# InterfaceConnector.net
KiCad netlist of a schematic drawn in Altium Designer
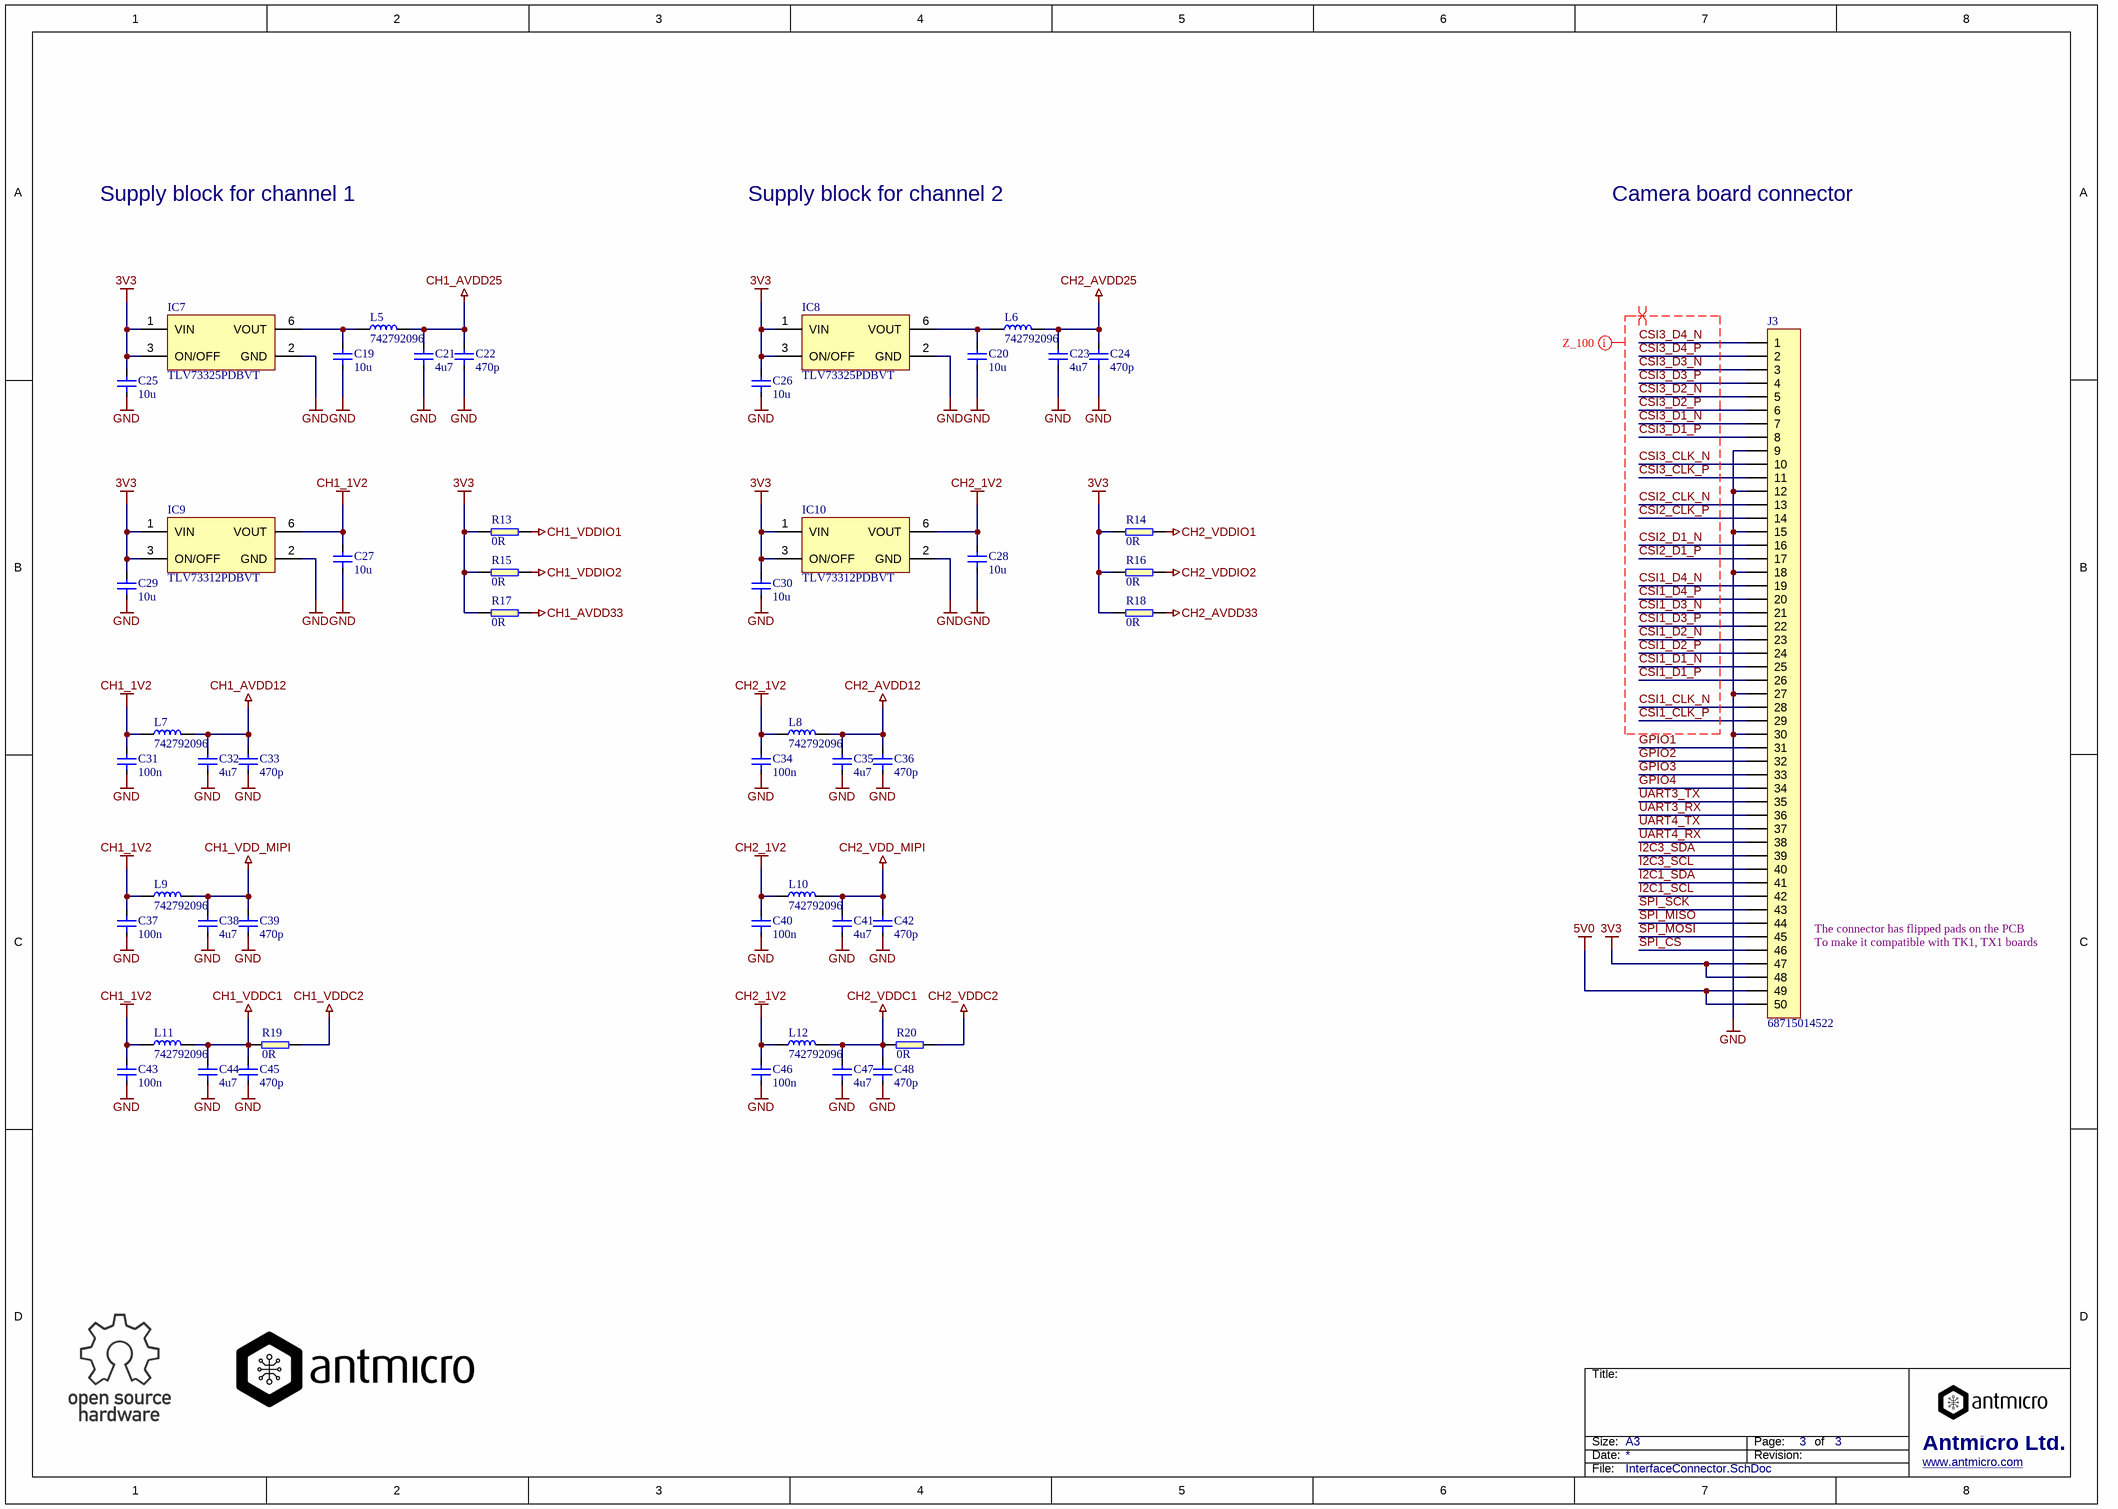
[diagram p0: InterfaceConnector.SchDoc]

(export (version "E")
  (design (tool "Eeschema 10.0.6"))
  (components
    (comp (ref "C19")
      (value "10u")
      (footprint "HDMI-MIPI-Bridge:0603")
      (description "MLCC SMT Capacitor 10uF 0603")
      (fields (field (name "PART NUMBER") "C_10u_0603") (field (name "MANUFACTURER") "MULTICOMP"))
      (libsource (lib "AntmicroComponents") (part "C"))
    )
    (comp (ref "C20")
      (value "10u")
      (footprint "HDMI-MIPI-Bridge:0603")
      (description "MLCC SMT Capacitor 10uF 0603")
      (fields (field (name "PART NUMBER") "C_10u_0603") (field (name "MANUFACTURER") "MULTICOMP"))
      (libsource (lib "AntmicroComponents") (part "C"))
    )
    (comp (ref "C21")
      (value "4u7")
      (footprint "HDMI-MIPI-Bridge:0402")
      (description "MLCC SMT Capacitor 4u7F 0603")
      (fields (field (name "PART NUMBER") "C_4u7_0402") (field (name "MANUFACTURER") "MURATA"))
      (libsource (lib "AntmicroComponents") (part "C"))
    )
    (comp (ref "C22")
      (value "470p")
      (footprint "HDMI-MIPI-Bridge:0402")
      (description "MLCC SMT Capacitor 470pF 0402")
      (fields (field (name "PART NUMBER") "C_470p_0402") (field (name "MANUFACTURER") "MULTICOMP"))
      (libsource (lib "AntmicroComponents") (part "C"))
    )
    (comp (ref "C23")
      (value "4u7")
      (footprint "HDMI-MIPI-Bridge:0402")
      (description "MLCC SMT Capacitor 4u7F 0603")
      (fields (field (name "PART NUMBER") "C_4u7_0402") (field (name "MANUFACTURER") "MURATA"))
      (libsource (lib "AntmicroComponents") (part "C"))
    )
    (comp (ref "C24")
      (value "470p")
      (footprint "HDMI-MIPI-Bridge:0402")
      (description "MLCC SMT Capacitor 470pF 0402")
      (fields (field (name "PART NUMBER") "C_470p_0402") (field (name "MANUFACTURER") "MULTICOMP"))
      (libsource (lib "AntmicroComponents") (part "C"))
    )
    (comp (ref "C25")
      (value "10u")
      (footprint "HDMI-MIPI-Bridge:0603")
      (description "MLCC SMT Capacitor 10uF 0603")
      (fields (field (name "PART NUMBER") "C_10u_0603") (field (name "MANUFACTURER") "MULTICOMP"))
      (libsource (lib "AntmicroComponents") (part "C"))
    )
    (comp (ref "C26")
      (value "10u")
      (footprint "HDMI-MIPI-Bridge:0603")
      (description "MLCC SMT Capacitor 10uF 0603")
      (fields (field (name "PART NUMBER") "C_10u_0603") (field (name "MANUFACTURER") "MULTICOMP"))
      (libsource (lib "AntmicroComponents") (part "C"))
    )
    (comp (ref "C27")
      (value "10u")
      (footprint "HDMI-MIPI-Bridge:0603")
      (description "MLCC SMT Capacitor 10uF 0603")
      (fields (field (name "PART NUMBER") "C_10u_0603") (field (name "MANUFACTURER") "MULTICOMP"))
      (libsource (lib "AntmicroComponents") (part "C"))
    )
    (comp (ref "C28")
      (value "10u")
      (footprint "HDMI-MIPI-Bridge:0603")
      (description "MLCC SMT Capacitor 10uF 0603")
      (fields (field (name "PART NUMBER") "C_10u_0603") (field (name "MANUFACTURER") "MULTICOMP"))
      (libsource (lib "AntmicroComponents") (part "C"))
    )
    (comp (ref "C29")
      (value "10u")
      (footprint "HDMI-MIPI-Bridge:0603")
      (description "MLCC SMT Capacitor 10uF 0603")
      (fields (field (name "PART NUMBER") "C_10u_0603") (field (name "MANUFACTURER") "MULTICOMP"))
      (libsource (lib "AntmicroComponents") (part "C"))
    )
    (comp (ref "C30")
      (value "10u")
      (footprint "HDMI-MIPI-Bridge:0603")
      (description "MLCC SMT Capacitor 10uF 0603")
      (fields (field (name "PART NUMBER") "C_10u_0603") (field (name "MANUFACTURER") "MULTICOMP"))
      (libsource (lib "AntmicroComponents") (part "C"))
    )
    (comp (ref "C31")
      (value "100n")
      (footprint "HDMI-MIPI-Bridge:0402")
      (description "MLCC SMT Capacitor 100nF 0402")
      (fields (field (name "PART NUMBER") "C_100n_0402") (field (name "MANUFACTURER") "MULTICOMP"))
      (libsource (lib "AntmicroComponents") (part "C"))
    )
    (comp (ref "C32")
      (value "4u7")
      (footprint "HDMI-MIPI-Bridge:0402")
      (description "MLCC SMT Capacitor 4u7F 0603")
      (fields (field (name "PART NUMBER") "C_4u7_0402") (field (name "MANUFACTURER") "MURATA"))
      (libsource (lib "AntmicroComponents") (part "C"))
    )
    (comp (ref "C33")
      (value "470p")
      (footprint "HDMI-MIPI-Bridge:0402")
      (description "MLCC SMT Capacitor 470pF 0402")
      (fields (field (name "PART NUMBER") "C_470p_0402") (field (name "MANUFACTURER") "MULTICOMP"))
      (libsource (lib "AntmicroComponents") (part "C"))
    )
    (comp (ref "C34")
      (value "100n")
      (footprint "HDMI-MIPI-Bridge:0402")
      (description "MLCC SMT Capacitor 100nF 0402")
      (fields (field (name "PART NUMBER") "C_100n_0402") (field (name "MANUFACTURER") "MULTICOMP"))
      (libsource (lib "AntmicroComponents") (part "C"))
    )
    (comp (ref "C35")
      (value "4u7")
      (footprint "HDMI-MIPI-Bridge:0402")
      (description "MLCC SMT Capacitor 4u7F 0603")
      (fields (field (name "PART NUMBER") "C_4u7_0402") (field (name "MANUFACTURER") "MURATA"))
      (libsource (lib "AntmicroComponents") (part "C"))
    )
    (comp (ref "C36")
      (value "470p")
      (footprint "HDMI-MIPI-Bridge:0402")
      (description "MLCC SMT Capacitor 470pF 0402")
      (fields (field (name "PART NUMBER") "C_470p_0402") (field (name "MANUFACTURER") "MULTICOMP"))
      (libsource (lib "AntmicroComponents") (part "C"))
    )
    (comp (ref "C37")
      (value "100n")
      (footprint "HDMI-MIPI-Bridge:0402")
      (description "MLCC SMT Capacitor 100nF 0402")
      (fields (field (name "PART NUMBER") "C_100n_0402") (field (name "MANUFACTURER") "MULTICOMP"))
      (libsource (lib "AntmicroComponents") (part "C"))
    )
    (comp (ref "C38")
      (value "4u7")
      (footprint "HDMI-MIPI-Bridge:0402")
      (description "MLCC SMT Capacitor 4u7F 0603")
      (fields (field (name "PART NUMBER") "C_4u7_0402") (field (name "MANUFACTURER") "MURATA"))
      (libsource (lib "AntmicroComponents") (part "C"))
    )
    (comp (ref "C39")
      (value "470p")
      (footprint "HDMI-MIPI-Bridge:0402")
      (description "MLCC SMT Capacitor 470pF 0402")
      (fields (field (name "PART NUMBER") "C_470p_0402") (field (name "MANUFACTURER") "MULTICOMP"))
      (libsource (lib "AntmicroComponents") (part "C"))
    )
    (comp (ref "C40")
      (value "100n")
      (footprint "HDMI-MIPI-Bridge:0402")
      (description "MLCC SMT Capacitor 100nF 0402")
      (fields (field (name "PART NUMBER") "C_100n_0402") (field (name "MANUFACTURER") "MULTICOMP"))
      (libsource (lib "AntmicroComponents") (part "C"))
    )
    (comp (ref "C41")
      (value "4u7")
      (footprint "HDMI-MIPI-Bridge:0402")
      (description "MLCC SMT Capacitor 4u7F 0603")
      (fields (field (name "PART NUMBER") "C_4u7_0402") (field (name "MANUFACTURER") "MURATA"))
      (libsource (lib "AntmicroComponents") (part "C"))
    )
    (comp (ref "C42")
      (value "470p")
      (footprint "HDMI-MIPI-Bridge:0402")
      (description "MLCC SMT Capacitor 470pF 0402")
      (fields (field (name "PART NUMBER") "C_470p_0402") (field (name "MANUFACTURER") "MULTICOMP"))
      (libsource (lib "AntmicroComponents") (part "C"))
    )
    (comp (ref "C43")
      (value "100n")
      (footprint "HDMI-MIPI-Bridge:0402")
      (description "MLCC SMT Capacitor 100nF 0402")
      (fields (field (name "PART NUMBER") "C_100n_0402") (field (name "MANUFACTURER") "MULTICOMP"))
      (libsource (lib "AntmicroComponents") (part "C"))
    )
    (comp (ref "C44")
      (value "4u7")
      (footprint "HDMI-MIPI-Bridge:0402")
      (description "MLCC SMT Capacitor 4u7F 0603")
      (fields (field (name "PART NUMBER") "C_4u7_0402") (field (name "MANUFACTURER") "MURATA"))
      (libsource (lib "AntmicroComponents") (part "C"))
    )
    (comp (ref "C45")
      (value "470p")
      (footprint "HDMI-MIPI-Bridge:0402")
      (description "MLCC SMT Capacitor 470pF 0402")
      (fields (field (name "PART NUMBER") "C_470p_0402") (field (name "MANUFACTURER") "MULTICOMP"))
      (libsource (lib "AntmicroComponents") (part "C"))
    )
    (comp (ref "C46")
      (value "100n")
      (footprint "HDMI-MIPI-Bridge:0402")
      (description "MLCC SMT Capacitor 100nF 0402")
      (fields (field (name "PART NUMBER") "C_100n_0402") (field (name "MANUFACTURER") "MULTICOMP"))
      (libsource (lib "AntmicroComponents") (part "C"))
    )
    (comp (ref "C47")
      (value "4u7")
      (footprint "HDMI-MIPI-Bridge:0402")
      (description "MLCC SMT Capacitor 4u7F 0603")
      (fields (field (name "PART NUMBER") "C_4u7_0402") (field (name "MANUFACTURER") "MURATA"))
      (libsource (lib "AntmicroComponents") (part "C"))
    )
    (comp (ref "C48")
      (value "470p")
      (footprint "HDMI-MIPI-Bridge:0402")
      (description "MLCC SMT Capacitor 470pF 0402")
      (fields (field (name "PART NUMBER") "C_470p_0402") (field (name "MANUFACTURER") "MULTICOMP"))
      (libsource (lib "AntmicroComponents") (part "C"))
    )
    (comp (ref "IC7")
      (value "TLV73325PDBVT")
      (footprint "HDMI-MIPI-Bridge:SOT23-5N")
      (description "Linear Voltage Regulator IC Positive Fixed Output 2.5V 300mA SOT-23-5")
      (fields (field (name "MANUFACTURER") "TEXAS INSTRUMENTS"))
      (libsource (lib "AntmicroComponents") (part "VREG_EN"))
    )
    (comp (ref "IC8")
      (value "TLV73325PDBVT")
      (footprint "HDMI-MIPI-Bridge:SOT23-5N")
      (description "Linear Voltage Regulator IC Positive Fixed Output 2.5V 300mA SOT-23-5")
      (fields (field (name "MANUFACTURER") "TEXAS INSTRUMENTS"))
      (libsource (lib "AntmicroComponents") (part "VREG_EN"))
    )
    (comp (ref "IC9")
      (value "TLV73312PDBVT")
      (footprint "HDMI-MIPI-Bridge:SOT23-5N")
      (description "Linear Voltage Regulator IC Positive Fixed Output 3.3V 300mA SOT-23-5")
      (fields (field (name "MANUFACTURER") "TEXAS INSTRUMENTS"))
      (libsource (lib "AntmicroComponents") (part "VREG_EN"))
    )
    (comp (ref "IC10")
      (value "TLV73312PDBVT")
      (footprint "HDMI-MIPI-Bridge:SOT23-5N")
      (description "Linear Voltage Regulator IC Positive Fixed Output 3.3V 300mA SOT-23-5")
      (fields (field (name "MANUFACTURER") "TEXAS INSTRUMENTS"))
      (libsource (lib "AntmicroComponents") (part "VREG_EN"))
    )
    (comp (ref "J3")
      (value "68715014522")
      (footprint "HDMI-MIPI-Bridge:68715014522_FLIPPED")
      (description "0.50mm SMT ZIF Horizontal Bottom Contact WR-FPC")
      (fields
        (field (name "PART NUMBER") "WE-687-150-145-22_FLIPPED")
        (field (name "MANUFACTURER") "WURTH ELEKTRONIK")
      )
      (libsource (lib "AntmicroComponents") (part "1X50"))
    )
    (comp (ref "L5")
      (value "742792096")
      (footprint "HDMI-MIPI-Bridge:0805")
      (description "FERRITE BEAD, 1kOhm 1A")
      (fields (field (name "PART NUMBER") "Wurth-742792096") (field (name "MANUFACTURER") "WURTH ELEKTRONIK"))
      (libsource (lib "AntmicroComponents") (part "Inductor SMT"))
    )
    (comp (ref "L6")
      (value "742792096")
      (footprint "HDMI-MIPI-Bridge:0805")
      (description "FERRITE BEAD, 1kOhm 1A")
      (fields (field (name "PART NUMBER") "Wurth-742792096") (field (name "MANUFACTURER") "WURTH ELEKTRONIK"))
      (libsource (lib "AntmicroComponents") (part "Inductor SMT"))
    )
    (comp (ref "L7")
      (value "742792096")
      (footprint "HDMI-MIPI-Bridge:0805")
      (description "FERRITE BEAD, 1kOhm 1A")
      (fields (field (name "PART NUMBER") "Wurth-742792096") (field (name "MANUFACTURER") "WURTH ELEKTRONIK"))
      (libsource (lib "AntmicroComponents") (part "Inductor SMT"))
    )
    (comp (ref "L8")
      (value "742792096")
      (footprint "HDMI-MIPI-Bridge:0805")
      (description "FERRITE BEAD, 1kOhm 1A")
      (fields (field (name "PART NUMBER") "Wurth-742792096") (field (name "MANUFACTURER") "WURTH ELEKTRONIK"))
      (libsource (lib "AntmicroComponents") (part "Inductor SMT"))
    )
    (comp (ref "L9")
      (value "742792096")
      (footprint "HDMI-MIPI-Bridge:0805")
      (description "FERRITE BEAD, 1kOhm 1A")
      (fields (field (name "PART NUMBER") "Wurth-742792096") (field (name "MANUFACTURER") "WURTH ELEKTRONIK"))
      (libsource (lib "AntmicroComponents") (part "Inductor SMT"))
    )
    (comp (ref "L10")
      (value "742792096")
      (footprint "HDMI-MIPI-Bridge:0805")
      (description "FERRITE BEAD, 1kOhm 1A")
      (fields (field (name "PART NUMBER") "Wurth-742792096") (field (name "MANUFACTURER") "WURTH ELEKTRONIK"))
      (libsource (lib "AntmicroComponents") (part "Inductor SMT"))
    )
    (comp (ref "L11")
      (value "742792096")
      (footprint "HDMI-MIPI-Bridge:0805")
      (description "FERRITE BEAD, 1kOhm 1A")
      (fields (field (name "PART NUMBER") "Wurth-742792096") (field (name "MANUFACTURER") "WURTH ELEKTRONIK"))
      (libsource (lib "AntmicroComponents") (part "Inductor SMT"))
    )
    (comp (ref "L12")
      (value "742792096")
      (footprint "HDMI-MIPI-Bridge:0805")
      (description "FERRITE BEAD, 1kOhm 1A")
      (fields (field (name "PART NUMBER") "Wurth-742792096") (field (name "MANUFACTURER") "WURTH ELEKTRONIK"))
      (libsource (lib "AntmicroComponents") (part "Inductor SMT"))
    )
    (comp (ref "R13")
      (value "0R")
      (footprint "HDMI-MIPI-Bridge:0603")
      (description "SMT Resistor 0R 0603")
      (fields (field (name "PART NUMBER") "R_0R_0603") (field (name "MANUFACTURER") "BOURNS"))
      (libsource (lib "AntmicroComponents") (part "R"))
    )
    (comp (ref "R14")
      (value "0R")
      (footprint "HDMI-MIPI-Bridge:0603")
      (description "SMT Resistor 0R 0603")
      (fields (field (name "PART NUMBER") "R_0R_0603") (field (name "MANUFACTURER") "BOURNS"))
      (libsource (lib "AntmicroComponents") (part "R"))
    )
    (comp (ref "R15")
      (value "0R")
      (footprint "HDMI-MIPI-Bridge:0603")
      (description "SMT Resistor 0R 0603")
      (fields (field (name "PART NUMBER") "R_0R_0603") (field (name "MANUFACTURER") "BOURNS"))
      (libsource (lib "AntmicroComponents") (part "R"))
    )
    (comp (ref "R16")
      (value "0R")
      (footprint "HDMI-MIPI-Bridge:0603")
      (description "SMT Resistor 0R 0603")
      (fields (field (name "PART NUMBER") "R_0R_0603") (field (name "MANUFACTURER") "BOURNS"))
      (libsource (lib "AntmicroComponents") (part "R"))
    )
    (comp (ref "R17")
      (value "0R")
      (footprint "HDMI-MIPI-Bridge:0603")
      (description "SMT Resistor 0R 0603")
      (fields (field (name "PART NUMBER") "R_0R_0603") (field (name "MANUFACTURER") "BOURNS"))
      (libsource (lib "AntmicroComponents") (part "R"))
    )
    (comp (ref "R18")
      (value "0R")
      (footprint "HDMI-MIPI-Bridge:0603")
      (description "SMT Resistor 0R 0603")
      (fields (field (name "PART NUMBER") "R_0R_0603") (field (name "MANUFACTURER") "BOURNS"))
      (libsource (lib "AntmicroComponents") (part "R"))
    )
    (comp (ref "R19")
      (value "0R")
      (footprint "HDMI-MIPI-Bridge:0603")
      (description "SMT Resistor 0R 0603")
      (fields (field (name "PART NUMBER") "R_0R_0603") (field (name "MANUFACTURER") "BOURNS"))
      (libsource (lib "AntmicroComponents") (part "R"))
    )
    (comp (ref "R20")
      (value "0R")
      (footprint "HDMI-MIPI-Bridge:0603")
      (description "SMT Resistor 0R 0603")
      (fields (field (name "PART NUMBER") "R_0R_0603") (field (name "MANUFACTURER") "BOURNS"))
      (libsource (lib "AntmicroComponents") (part "R"))
    )
  )
  (nets
    (net (code "1") (name "/CSI1_CLK_N") (class "Default")
      (node (ref "J3") (pin "28") (pinfunction "28_28") (pintype "passive"))
    )
    (net (code "2") (name "/CSI1_CLK_P") (class "Default")
      (node (ref "J3") (pin "29") (pinfunction "29_29") (pintype "passive"))
    )
    (net (code "3") (name "/CSI1_D1_N") (class "Default")
      (node (ref "J3") (pin "25") (pinfunction "25_25") (pintype "passive"))
    )
    (net (code "4") (name "/CSI1_D1_P") (class "Default")
      (node (ref "J3") (pin "26") (pinfunction "26_26") (pintype "passive"))
    )
    (net (code "5") (name "/CSI1_D2_N") (class "Default")
      (node (ref "J3") (pin "23") (pinfunction "23_23") (pintype "passive"))
    )
    (net (code "6") (name "/CSI1_D2_P") (class "Default")
      (node (ref "J3") (pin "24") (pinfunction "24_24") (pintype "passive"))
    )
    (net (code "7") (name "/CSI1_D3_N") (class "Default")
      (node (ref "J3") (pin "21") (pinfunction "21_21") (pintype "passive"))
    )
    (net (code "8") (name "/CSI1_D3_P") (class "Default")
      (node (ref "J3") (pin "22") (pinfunction "22_22") (pintype "passive"))
    )
    (net (code "9") (name "/CSI1_D4_N") (class "Default")
      (node (ref "J3") (pin "19") (pinfunction "19_19") (pintype "passive"))
    )
    (net (code "10") (name "/CSI1_D4_P") (class "Default")
      (node (ref "J3") (pin "20") (pinfunction "20_20") (pintype "passive"))
    )
    (net (code "11") (name "/CSI2_CLK_N") (class "Default")
      (node (ref "J3") (pin "13") (pinfunction "13_13") (pintype "passive"))
    )
    (net (code "12") (name "/CSI2_CLK_P") (class "Default")
      (node (ref "J3") (pin "14") (pinfunction "14_14") (pintype "passive"))
    )
    (net (code "13") (name "/CSI2_D1_N") (class "Default")
      (node (ref "J3") (pin "16") (pinfunction "16_16") (pintype "passive"))
    )
    (net (code "14") (name "/CSI2_D1_P") (class "Default")
      (node (ref "J3") (pin "17") (pinfunction "17_17") (pintype "passive"))
    )
    (net (code "15") (name "/CSI3_CLK_N") (class "Default")
      (node (ref "J3") (pin "10") (pinfunction "10_10") (pintype "passive"))
    )
    (net (code "16") (name "/CSI3_CLK_P") (class "Default")
      (node (ref "J3") (pin "11") (pinfunction "11_11") (pintype "passive"))
    )
    (net (code "17") (name "/CSI3_D1_N") (class "Default")
      (node (ref "J3") (pin "7") (pinfunction "7_7") (pintype "passive"))
    )
    (net (code "18") (name "/CSI3_D1_P") (class "Default")
      (node (ref "J3") (pin "8") (pinfunction "8_8") (pintype "passive"))
    )
    (net (code "19") (name "/CSI3_D2_N") (class "Default")
      (node (ref "J3") (pin "5") (pinfunction "5_5") (pintype "passive"))
    )
    (net (code "20") (name "/CSI3_D2_P") (class "Default")
      (node (ref "J3") (pin "6") (pinfunction "6_6") (pintype "passive"))
    )
    (net (code "21") (name "/CSI3_D3_N") (class "Default")
      (node (ref "J3") (pin "3") (pinfunction "3_3") (pintype "passive"))
    )
    (net (code "22") (name "/CSI3_D3_P") (class "Default")
      (node (ref "J3") (pin "4") (pinfunction "4_4") (pintype "passive"))
    )
    (net (code "23") (name "/CSI3_D4_N") (class "Default")
      (node (ref "J3") (pin "1") (pinfunction "1_1") (pintype "passive"))
    )
    (net (code "24") (name "/CSI3_D4_P") (class "Default")
      (node (ref "J3") (pin "2") (pinfunction "2_2") (pintype "passive"))
    )
    (net (code "25") (name "/GPIO1") (class "Default")
      (node (ref "J3") (pin "31") (pinfunction "31_31") (pintype "passive"))
    )
    (net (code "26") (name "/GPIO2") (class "Default")
      (node (ref "J3") (pin "32") (pinfunction "32_32") (pintype "passive"))
    )
    (net (code "27") (name "/GPIO3") (class "Default")
      (node (ref "J3") (pin "33") (pinfunction "33_33") (pintype "passive"))
    )
    (net (code "28") (name "/GPIO4") (class "Default")
      (node (ref "J3") (pin "34") (pinfunction "34_34") (pintype "passive"))
    )
    (net (code "29") (name "/I2C1_SCL") (class "Default")
      (node (ref "J3") (pin "42") (pinfunction "42_42") (pintype "passive"))
    )
    (net (code "30") (name "/I2C1_SDA") (class "Default")
      (node (ref "J3") (pin "41") (pinfunction "41_41") (pintype "passive"))
    )
    (net (code "31") (name "/I2C3_SCL") (class "Default")
      (node (ref "J3") (pin "40") (pinfunction "40_40") (pintype "passive"))
    )
    (net (code "32") (name "/I2C3_SDA") (class "Default")
      (node (ref "J3") (pin "39") (pinfunction "39_39") (pintype "passive"))
    )
    (net (code "33") (name "/SPI_CS") (class "Default")
      (node (ref "J3") (pin "46") (pinfunction "46_46") (pintype "passive"))
    )
    (net (code "34") (name "/SPI_MISO") (class "Default")
      (node (ref "J3") (pin "44") (pinfunction "44_44") (pintype "passive"))
    )
    (net (code "35") (name "/SPI_MOSI") (class "Default")
      (node (ref "J3") (pin "45") (pinfunction "45_45") (pintype "passive"))
    )
    (net (code "36") (name "/SPI_SCK") (class "Default")
      (node (ref "J3") (pin "43") (pinfunction "43_43") (pintype "passive"))
    )
    (net (code "37") (name "/UART3_RX") (class "Default")
      (node (ref "J3") (pin "36") (pinfunction "36_36") (pintype "passive"))
    )
    (net (code "38") (name "/UART3_TX") (class "Default")
      (node (ref "J3") (pin "35") (pinfunction "35_35") (pintype "passive"))
    )
    (net (code "39") (name "/UART4_RX") (class "Default")
      (node (ref "J3") (pin "38") (pinfunction "38_38") (pintype "passive"))
    )
    (net (code "40") (name "/UART4_TX") (class "Default")
      (node (ref "J3") (pin "37") (pinfunction "37_37") (pintype "passive"))
    )
    (net (code "41") (name "3V3") (class "Default")
      (node (ref "C25") (pin "2") (pinfunction "2_2") (pintype "passive"))
      (node (ref "C26") (pin "2") (pinfunction "2_2") (pintype "passive"))
      (node (ref "C29") (pin "2") (pinfunction "2_2") (pintype "passive"))
      (node (ref "C30") (pin "2") (pinfunction "2_2") (pintype "passive"))
      (node (ref "IC10") (pin "1") (pinfunction "VIN_1") (pintype "passive"))
      (node (ref "IC10") (pin "3") (pinfunction "ON/OFF_3") (pintype "passive"))
      (node (ref "IC7") (pin "1") (pinfunction "VIN_1") (pintype "passive"))
      (node (ref "IC7") (pin "3") (pinfunction "ON/OFF_3") (pintype "passive"))
      (node (ref "IC8") (pin "1") (pinfunction "VIN_1") (pintype "passive"))
      (node (ref "IC8") (pin "3") (pinfunction "ON/OFF_3") (pintype "passive"))
      (node (ref "IC9") (pin "1") (pinfunction "VIN_1") (pintype "passive"))
      (node (ref "IC9") (pin "3") (pinfunction "ON/OFF_3") (pintype "passive"))
      (node (ref "J3") (pin "47") (pinfunction "47_47") (pintype "passive"))
      (node (ref "J3") (pin "48") (pinfunction "48_48") (pintype "passive"))
      (node (ref "R13") (pin "1") (pintype "passive"))
      (node (ref "R14") (pin "1") (pintype "passive"))
      (node (ref "R15") (pin "1") (pintype "passive"))
      (node (ref "R16") (pin "1") (pintype "passive"))
      (node (ref "R17") (pin "1") (pintype "passive"))
      (node (ref "R18") (pin "1") (pintype "passive"))
    )
    (net (code "42") (name "5V0") (class "Default")
      (node (ref "J3") (pin "49") (pinfunction "49_49") (pintype "passive"))
      (node (ref "J3") (pin "50") (pinfunction "50_50") (pintype "passive"))
    )
    (net (code "43") (name "CH1_1V2") (class "Default")
      (node (ref "C27") (pin "2") (pinfunction "2_2") (pintype "passive"))
      (node (ref "C31") (pin "2") (pinfunction "2_2") (pintype "passive"))
      (node (ref "C37") (pin "2") (pinfunction "2_2") (pintype "passive"))
      (node (ref "C43") (pin "2") (pinfunction "2_2") (pintype "passive"))
      (node (ref "IC9") (pin "6") (pinfunction "VOUT_6") (pintype "passive"))
      (node (ref "L11") (pin "1") (pintype "passive"))
      (node (ref "L7") (pin "1") (pintype "passive"))
      (node (ref "L9") (pin "1") (pintype "passive"))
    )
    (net (code "44") (name "CH1_AVDD12") (class "Default")
      (node (ref "C32") (pin "2") (pinfunction "2_2") (pintype "passive"))
      (node (ref "C33") (pin "2") (pinfunction "2_2") (pintype "passive"))
      (node (ref "L7") (pin "2") (pintype "passive"))
    )
    (net (code "45") (name "CH1_AVDD25") (class "Default")
      (node (ref "C21") (pin "2") (pinfunction "2_2") (pintype "passive"))
      (node (ref "C22") (pin "2") (pinfunction "2_2") (pintype "passive"))
      (node (ref "L5") (pin "2") (pintype "passive"))
    )
    (net (code "46") (name "CH1_AVDD33") (class "Default") (node (ref "R17") (pin "2") (pintype "passive")))
    (net (code "47") (name "CH1_VDDC1") (class "Default")
      (node (ref "C44") (pin "2") (pinfunction "2_2") (pintype "passive"))
      (node (ref "C45") (pin "2") (pinfunction "2_2") (pintype "passive"))
      (node (ref "L11") (pin "2") (pintype "passive"))
      (node (ref "R19") (pin "1") (pintype "passive"))
    )
    (net (code "48") (name "CH1_VDDC2") (class "Default") (node (ref "R19") (pin "2") (pintype "passive")))
    (net (code "49") (name "CH1_VDDIO1") (class "Default") (node (ref "R13") (pin "2") (pintype "passive")))
    (net (code "50") (name "CH1_VDDIO2") (class "Default") (node (ref "R15") (pin "2") (pintype "passive")))
    (net (code "51") (name "CH1_VDD_MIPI") (class "Default")
      (node (ref "C38") (pin "2") (pinfunction "2_2") (pintype "passive"))
      (node (ref "C39") (pin "2") (pinfunction "2_2") (pintype "passive"))
      (node (ref "L9") (pin "2") (pintype "passive"))
    )
    (net (code "52") (name "CH2_1V2") (class "Default")
      (node (ref "C28") (pin "2") (pinfunction "2_2") (pintype "passive"))
      (node (ref "C34") (pin "2") (pinfunction "2_2") (pintype "passive"))
      (node (ref "C40") (pin "2") (pinfunction "2_2") (pintype "passive"))
      (node (ref "C46") (pin "2") (pinfunction "2_2") (pintype "passive"))
      (node (ref "IC10") (pin "6") (pinfunction "VOUT_6") (pintype "passive"))
      (node (ref "L10") (pin "1") (pintype "passive"))
      (node (ref "L12") (pin "1") (pintype "passive"))
      (node (ref "L8") (pin "1") (pintype "passive"))
    )
    (net (code "53") (name "CH2_AVDD12") (class "Default")
      (node (ref "C35") (pin "2") (pinfunction "2_2") (pintype "passive"))
      (node (ref "C36") (pin "2") (pinfunction "2_2") (pintype "passive"))
      (node (ref "L8") (pin "2") (pintype "passive"))
    )
    (net (code "54") (name "CH2_AVDD25") (class "Default")
      (node (ref "C23") (pin "2") (pinfunction "2_2") (pintype "passive"))
      (node (ref "C24") (pin "2") (pinfunction "2_2") (pintype "passive"))
      (node (ref "L6") (pin "2") (pintype "passive"))
    )
    (net (code "55") (name "CH2_AVDD33") (class "Default") (node (ref "R18") (pin "2") (pintype "passive")))
    (net (code "56") (name "CH2_VDDC1") (class "Default")
      (node (ref "C47") (pin "2") (pinfunction "2_2") (pintype "passive"))
      (node (ref "C48") (pin "2") (pinfunction "2_2") (pintype "passive"))
      (node (ref "L12") (pin "2") (pintype "passive"))
      (node (ref "R20") (pin "1") (pintype "passive"))
    )
    (net (code "57") (name "CH2_VDDC2") (class "Default") (node (ref "R20") (pin "2") (pintype "passive")))
    (net (code "58") (name "CH2_VDDIO1") (class "Default") (node (ref "R14") (pin "2") (pintype "passive")))
    (net (code "59") (name "CH2_VDDIO2") (class "Default") (node (ref "R16") (pin "2") (pintype "passive")))
    (net (code "60") (name "CH2_VDD_MIPI") (class "Default")
      (node (ref "C41") (pin "2") (pinfunction "2_2") (pintype "passive"))
      (node (ref "C42") (pin "2") (pinfunction "2_2") (pintype "passive"))
      (node (ref "L10") (pin "2") (pintype "passive"))
    )
    (net (code "61") (name "GND") (class "Default")
      (node (ref "C19") (pin "1") (pinfunction "1_1") (pintype "passive"))
      (node (ref "C20") (pin "1") (pinfunction "1_1") (pintype "passive"))
      (node (ref "C21") (pin "1") (pinfunction "1_1") (pintype "passive"))
      (node (ref "C22") (pin "1") (pinfunction "1_1") (pintype "passive"))
      (node (ref "C23") (pin "1") (pinfunction "1_1") (pintype "passive"))
      (node (ref "C24") (pin "1") (pinfunction "1_1") (pintype "passive"))
      (node (ref "C25") (pin "1") (pinfunction "1_1") (pintype "passive"))
      (node (ref "C26") (pin "1") (pinfunction "1_1") (pintype "passive"))
      (node (ref "C27") (pin "1") (pinfunction "1_1") (pintype "passive"))
      (node (ref "C28") (pin "1") (pinfunction "1_1") (pintype "passive"))
      (node (ref "C29") (pin "1") (pinfunction "1_1") (pintype "passive"))
      (node (ref "C30") (pin "1") (pinfunction "1_1") (pintype "passive"))
      (node (ref "C31") (pin "1") (pinfunction "1_1") (pintype "passive"))
      (node (ref "C32") (pin "1") (pinfunction "1_1") (pintype "passive"))
      (node (ref "C33") (pin "1") (pinfunction "1_1") (pintype "passive"))
      (node (ref "C34") (pin "1") (pinfunction "1_1") (pintype "passive"))
      (node (ref "C35") (pin "1") (pinfunction "1_1") (pintype "passive"))
      (node (ref "C36") (pin "1") (pinfunction "1_1") (pintype "passive"))
      (node (ref "C37") (pin "1") (pinfunction "1_1") (pintype "passive"))
      (node (ref "C38") (pin "1") (pinfunction "1_1") (pintype "passive"))
      (node (ref "C39") (pin "1") (pinfunction "1_1") (pintype "passive"))
      (node (ref "C40") (pin "1") (pinfunction "1_1") (pintype "passive"))
      (node (ref "C41") (pin "1") (pinfunction "1_1") (pintype "passive"))
      (node (ref "C42") (pin "1") (pinfunction "1_1") (pintype "passive"))
      (node (ref "C43") (pin "1") (pinfunction "1_1") (pintype "passive"))
      (node (ref "C44") (pin "1") (pinfunction "1_1") (pintype "passive"))
      (node (ref "C45") (pin "1") (pinfunction "1_1") (pintype "passive"))
      (node (ref "C46") (pin "1") (pinfunction "1_1") (pintype "passive"))
      (node (ref "C47") (pin "1") (pinfunction "1_1") (pintype "passive"))
      (node (ref "C48") (pin "1") (pinfunction "1_1") (pintype "passive"))
      (node (ref "IC10") (pin "2") (pinfunction "GND_2") (pintype "passive"))
      (node (ref "IC7") (pin "2") (pinfunction "GND_2") (pintype "passive"))
      (node (ref "IC8") (pin "2") (pinfunction "GND_2") (pintype "passive"))
      (node (ref "IC9") (pin "2") (pinfunction "GND_2") (pintype "passive"))
      (node (ref "J3") (pin "12") (pinfunction "12_12") (pintype "passive"))
      (node (ref "J3") (pin "15") (pinfunction "15_15") (pintype "passive"))
      (node (ref "J3") (pin "18") (pinfunction "18_18") (pintype "passive"))
      (node (ref "J3") (pin "27") (pinfunction "27_27") (pintype "passive"))
      (node (ref "J3") (pin "30") (pinfunction "30_30") (pintype "passive"))
      (node (ref "J3") (pin "9") (pinfunction "9_9") (pintype "passive"))
    )
    (net (code "62") (name "Net-(IC7-VOUT)") (class "Default")
      (node (ref "C19") (pin "2") (pinfunction "2_2") (pintype "passive"))
      (node (ref "IC7") (pin "6") (pinfunction "VOUT_6") (pintype "passive"))
      (node (ref "L5") (pin "1") (pintype "passive"))
    )
    (net (code "63") (name "Net-(IC8-VOUT)") (class "Default")
      (node (ref "C20") (pin "2") (pinfunction "2_2") (pintype "passive"))
      (node (ref "IC8") (pin "6") (pinfunction "VOUT_6") (pintype "passive"))
      (node (ref "L6") (pin "1") (pintype "passive"))
    )
  )
)
